# 11_-_MOSFET.net
KiCad netlist of a schematic drawn in Altium Designer
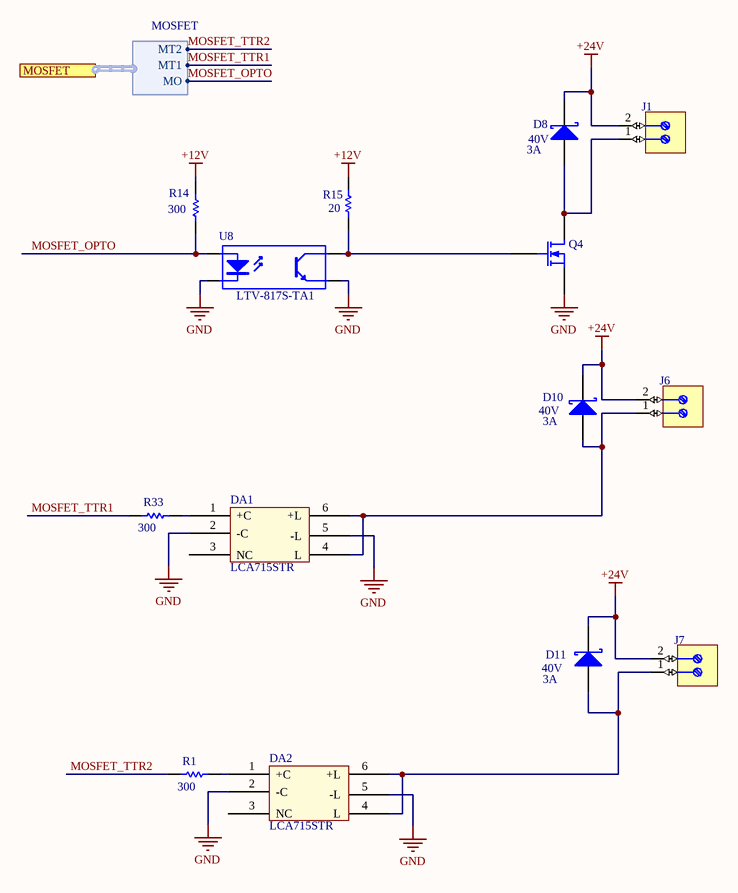
[diagram p0: [11] - MOSFET.SchDoc]

(export (version "E")
  (design (tool "Eeschema 10.0.6"))
  (components
    (comp (ref "D8")
      (value "SK32")
      (footprint "Blue Tractor-2021:D-Schottky")
      (description "Schottky Rectifier")
      (fields
        (field (name "MANUFACTURER") "Diodes")
        (field (name "MANUFACTURER PART NUMBER") "B340A-13-F")
        (field (name "OUTPUT CURRENT") "3A")
        (field (name "VOLTAGE") "40V")
      )
      (libsource (lib "GSMInformer-PB-TC.v1.0-2013") (part "SK32"))
    )
    (comp (ref "D10")
      (value "SK32")
      (footprint "Blue Tractor-2021:D-Schottky")
      (description "Schottky Rectifier")
      (fields
        (field (name "MANUFACTURER") "Diodes")
        (field (name "MANUFACTURER PART NUMBER") "B340A-13-F")
        (field (name "OUTPUT CURRENT") "3A")
        (field (name "VOLTAGE") "40V")
      )
      (libsource (lib "GSMInformer-PB-TC.v1.0-2013") (part "SK32"))
    )
    (comp (ref "D11")
      (value "SK32")
      (footprint "Blue Tractor-2021:D-Schottky")
      (description "Schottky Rectifier")
      (fields
        (field (name "MANUFACTURER") "Diodes")
        (field (name "MANUFACTURER PART NUMBER") "B340A-13-F")
        (field (name "OUTPUT CURRENT") "3A")
        (field (name "VOLTAGE") "40V")
      )
      (libsource (lib "GSMInformer-PB-TC.v1.0-2013") (part "SK32"))
    )
    (comp (ref "DA1")
      (value "LCA715STR")
      (footprint "Blue Tractor-2021:6-SMD")
      (description "LCA715S-TTP")
      (libsource (lib "Blue Tractor-2021") (part "LCA715STR"))
    )
    (comp (ref "DA2")
      (value "LCA715STR")
      (footprint "Blue Tractor-2021:6-SMD")
      (description "LCA715S-TTP")
      (libsource (lib "Blue Tractor-2021") (part "LCA715STR"))
    )
    (comp (ref "J1")
      (value "~")
      (footprint "Blue Tractor-2021:Connector -PHOENIX_1715721")
      (description "Connection -POENIX")
      (fields
        (field (name "PART NUMBER") "PHOENIX_1715721")
        (field (name "MANUFACTURER") "PHOENIX CONTACT")
        (field (name "AUTHOR") "CERN DEM JLC")
      )
      (libsource (lib "Blue Tractor-2021") (part "Connection 2 PIN"))
    )
    (comp (ref "J6")
      (value "~")
      (footprint "Blue Tractor-2021:Connector -PHOENIX_1715721")
      (description "Connection -POENIX")
      (fields
        (field (name "PART NUMBER") "PHOENIX_1715721")
        (field (name "MANUFACTURER") "PHOENIX CONTACT")
        (field (name "AUTHOR") "CERN DEM JLC")
      )
      (libsource (lib "Blue Tractor-2021") (part "Connection 2 PIN"))
    )
    (comp (ref "J7")
      (value "~")
      (footprint "Blue Tractor-2021:Connector -PHOENIX_1715721")
      (description "Connection -POENIX")
      (fields
        (field (name "PART NUMBER") "PHOENIX_1715721")
        (field (name "MANUFACTURER") "PHOENIX CONTACT")
        (field (name "AUTHOR") "CERN DEM JLC")
      )
      (libsource (lib "Blue Tractor-2021") (part "Connection 2 PIN"))
    )
    (comp (ref "Q4")
      (value "MOSFET-N")
      (footprint "D-PAK (TO-252)")
      (description "N-Channel MOSFET")
      (fields (field (name "PUBLISHER") "Altium Limited"))
      (libsource (lib "Miscellaneous Devices") (part "MOSFET-N"))
    )
    (comp (ref "R1")
      (value "300")
      (footprint "Blue Tractor-2021:0603_R")
      (description "Chip Resistor")
      (fields
        (field (name "MANUFACTURER") "Stackpole Electronics Inc")
        (field (name "MANUFACTURER PART NUMBER") "RMCF0603JT3K60")
        (field (name "PUBLISHER") "Altium Limited")
      )
      (libsource (lib "Altium_Library") (part "Res1"))
    )
    (comp (ref "R14")
      (value "Res1")
      (footprint "Blue Tractor-2021:0603_R")
      (description "Chip Resistor")
      (fields
        (field (name "MANUFACTURER") "Panasonic")
        (field (name "MANUFACTURER PART NUMBER") "ERJ-3GEYJ222V")
        (field (name "RESISTANCE") "300")
      )
      (libsource (lib "Altium_Library") (part "Res1"))
    )
    (comp (ref "R15")
      (value "Res1")
      (footprint "Blue Tractor-2021:0603_R")
      (description "Chip Resistor")
      (fields
        (field (name "MANUFACTURER") "Panasonic")
        (field (name "MANUFACTURER PART NUMBER") "ERJ-3GEYJ222V")
        (field (name "RESISTANCE") "20")
      )
      (libsource (lib "Altium_Library") (part "Res1"))
    )
    (comp (ref "R33")
      (value "300")
      (footprint "Blue Tractor-2021:0603_R")
      (description "Chip Resistor")
      (fields
        (field (name "MANUFACTURER") "Stackpole Electronics Inc")
        (field (name "MANUFACTURER PART NUMBER") "RMCF0603JT3K60")
        (field (name "PUBLISHER") "Altium Limited")
      )
      (libsource (lib "Altium_Library") (part "Res1"))
    )
    (comp (ref "U8")
      (value "Optoisolator1")
      (footprint "Blue Tractor-2021:LTV-817S_LTO-L")
      (description "4-Pin Phototransistor Optocoupler")
      (fields
        (field (name "MANUFACTURER") "Toshiba")
        (field (name "MANUFACTURER PART NUMBER") "LTV-817S-TA1")
      )
      (libsource (lib "Miscellaneous Devices") (part "Optoisolator1"))
    )
  )
  (nets
    (net (code "2") (name "+12V") (class "Default")
      (node (ref "R14") (pin "2") (pinfunction "2_2") (pintype "passive"))
      (node (ref "R15") (pin "2") (pinfunction "2_2") (pintype "passive"))
    )
    (net (code "3") (name "+24V") (class "Default")
      (node (ref "D10") (pin "2") (pinfunction "K_2") (pintype "passive"))
      (node (ref "D11") (pin "2") (pinfunction "K_2") (pintype "passive"))
      (node (ref "D8") (pin "2") (pinfunction "K_2") (pintype "passive"))
      (node (ref "J1") (pin "2") (pinfunction "2_2") (pintype "bidirectional"))
      (node (ref "J6") (pin "2") (pinfunction "2_2") (pintype "bidirectional"))
      (node (ref "J7") (pin "2") (pinfunction "2_2") (pintype "bidirectional"))
    )
    (net (code "4") (name "/MOSFET_OPTO") (class "Default")
      (node (ref "R14") (pin "1") (pinfunction "1_1") (pintype "passive"))
      (node (ref "U8") (pin "1") (pinfunction "A_1") (pintype "passive"))
    )
    (net (code "5") (name "/MOSFET_TTR1") (class "Default")
      (node (ref "R33") (pin "2") (pinfunction "2_2") (pintype "passive"))
    )
    (net (code "6") (name "/MOSFET_TTR2") (class "Default")
      (node (ref "R1") (pin "2") (pinfunction "2_2") (pintype "passive"))
    )
    (net (code "8") (name "GND") (class "Default")
      (node (ref "DA1") (pin "2") (pinfunction "-C_2") (pintype "power_in"))
      (node (ref "DA1") (pin "5") (pinfunction "-L_5") (pintype "power_in"))
      (node (ref "DA2") (pin "2") (pinfunction "-C_2") (pintype "power_in"))
      (node (ref "DA2") (pin "5") (pinfunction "-L_5") (pintype "power_in"))
      (node (ref "Q4") (pin "3") (pinfunction "S_3") (pintype "passive"))
      (node (ref "U8") (pin "2") (pinfunction "K_2") (pintype "passive"))
      (node (ref "U8") (pin "3") (pinfunction "E_3") (pintype "passive"))
    )
    (net (code "9") (name "Net-(D8-A)") (class "Default")
      (node (ref "D8") (pin "1") (pinfunction "A_1") (pintype "passive"))
      (node (ref "J1") (pin "1") (pinfunction "1_1") (pintype "bidirectional"))
      (node (ref "Q4") (pin "2") (pinfunction "D_2") (pintype "passive"))
    )
    (net (code "10") (name "Net-(D10-A)") (class "Default")
      (node (ref "D10") (pin "1") (pinfunction "A_1") (pintype "passive"))
      (node (ref "DA1") (pin "4") (pinfunction "L_4") (pintype "power_in"))
      (node (ref "DA1") (pin "6") (pinfunction "+L_6") (pintype "power_in"))
      (node (ref "J6") (pin "1") (pinfunction "1_1") (pintype "bidirectional"))
    )
    (net (code "11") (name "Net-(D11-A)") (class "Default")
      (node (ref "D11") (pin "1") (pinfunction "A_1") (pintype "passive"))
      (node (ref "DA2") (pin "4") (pinfunction "L_4") (pintype "power_in"))
      (node (ref "DA2") (pin "6") (pinfunction "+L_6") (pintype "power_in"))
      (node (ref "J7") (pin "1") (pinfunction "1_1") (pintype "bidirectional"))
    )
    (net (code "12") (name "Net-(DA1-+C)") (class "Default")
      (node (ref "DA1") (pin "1") (pinfunction "+C_1") (pintype "power_in"))
      (node (ref "R33") (pin "1") (pinfunction "1_1") (pintype "passive"))
    )
    (net (code "13") (name "Net-(DA2-+C)") (class "Default")
      (node (ref "DA2") (pin "1") (pinfunction "+C_1") (pintype "power_in"))
      (node (ref "R1") (pin "1") (pinfunction "1_1") (pintype "passive"))
    )
    (net (code "14") (name "Net-(Q4-G)") (class "Default")
      (node (ref "Q4") (pin "1") (pinfunction "G_1") (pintype "passive"))
      (node (ref "R15") (pin "1") (pinfunction "1_1") (pintype "passive"))
      (node (ref "U8") (pin "4") (pinfunction "C_4") (pintype "passive"))
    )
    (net (code "15") (name "unconnected-(DA1-NC-Pad3)") (class "Default")
      (node (ref "DA1") (pin "3") (pinfunction "NC_3") (pintype "power_in"))
    )
    (net (code "16") (name "unconnected-(DA2-NC-Pad3)") (class "Default")
      (node (ref "DA2") (pin "3") (pinfunction "NC_3") (pintype "power_in"))
    )
  )
)
